# schematic.net
KiCad netlist of a schematic drawn in EAGLE
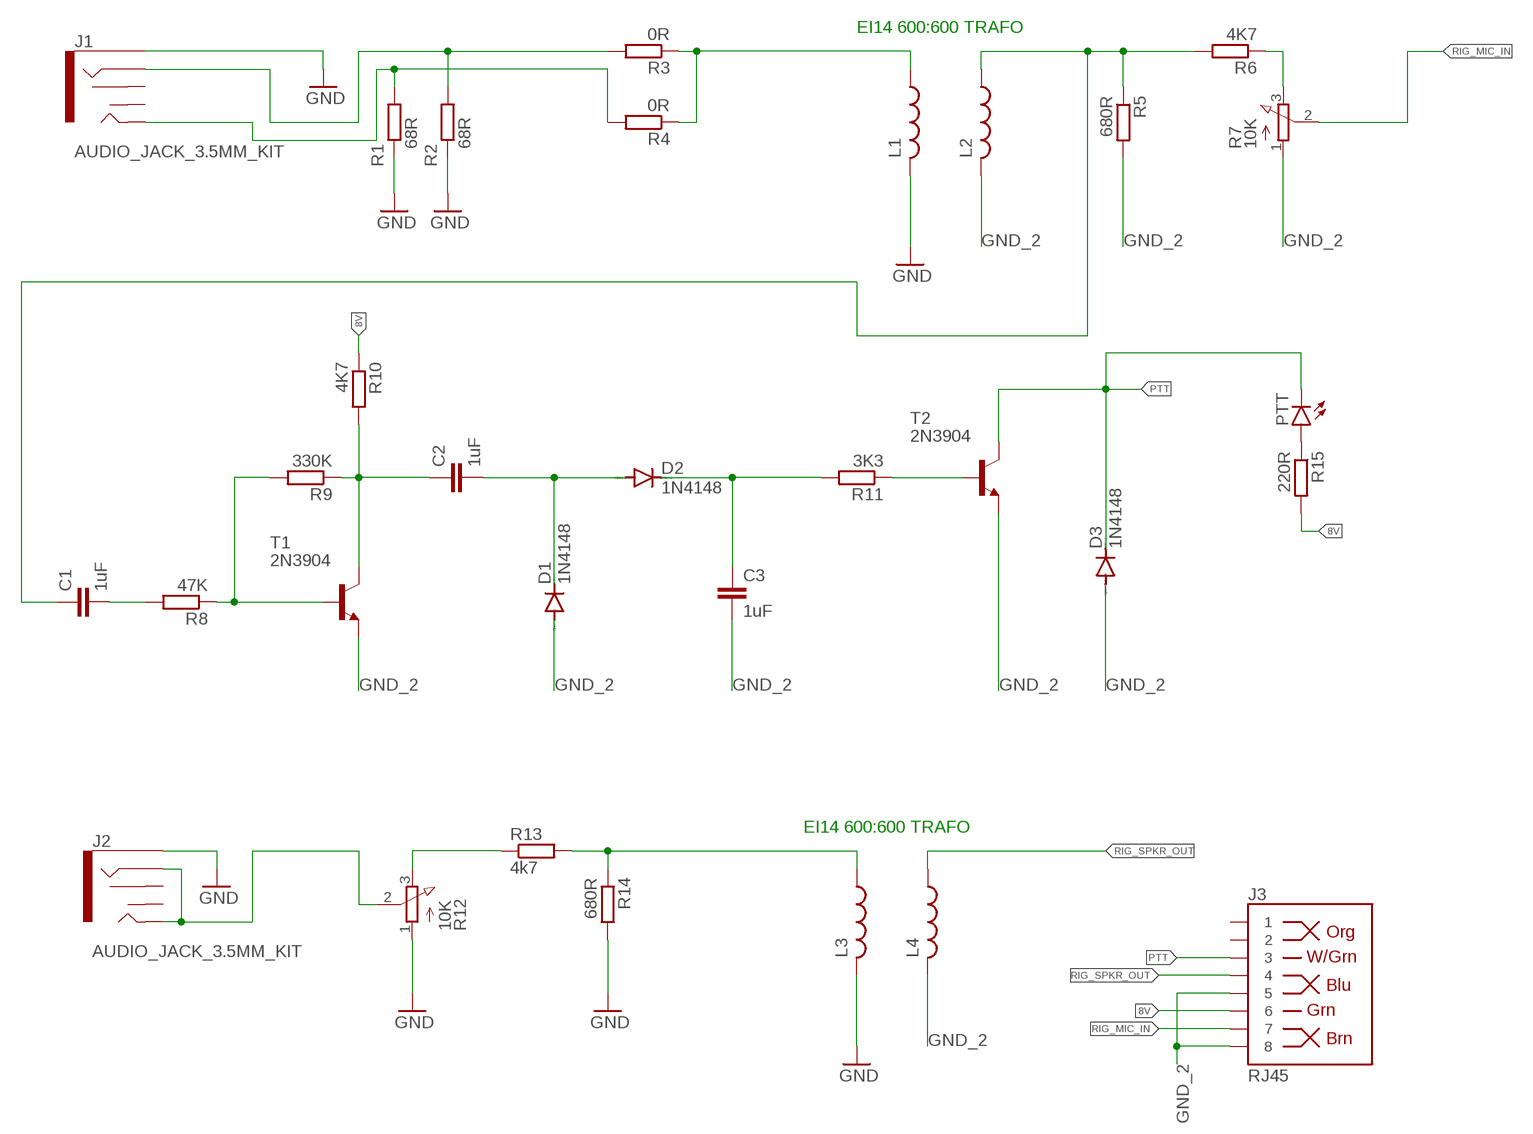
[diagram p0: schematic, sheet 1]

(export (version "E")
  (design (tool "Eeschema 10.0.6"))
  (components
    (comp (ref "C1")
      (value "1uF")
      (footprint "eagle-import:C025-030X050")
      (libsource (lib "eagle-import") (part "C-EU025-030X050"))
    )
    (comp (ref "C2")
      (value "1uF")
      (footprint "eagle-import:C025-030X050")
      (libsource (lib "eagle-import") (part "C-EU025-030X050"))
    )
    (comp (ref "C3")
      (value "1uF")
      (footprint "eagle-import:C025-030X050")
      (libsource (lib "eagle-import") (part "C-EU025-030X050"))
    )
    (comp (ref "D1")
      (value "1N4148")
      (footprint "eagle-import:DO35-7")
      (libsource (lib "eagle-import") (part "1N4148DO35-7"))
    )
    (comp (ref "D2")
      (value "1N4148")
      (footprint "eagle-import:DO35-7")
      (libsource (lib "eagle-import") (part "1N4148DO35-7"))
    )
    (comp (ref "D3")
      (value "1N4148")
      (footprint "eagle-import:DO35-7")
      (libsource (lib "eagle-import") (part "1N4148DO35-7"))
    )
    (comp (ref "J1")
      (value "AUDIO_JACK_3.5MM_KIT")
      (footprint "eagle-import:AUDIO-JACK-KIT")
      (libsource (lib "eagle-import") (part "AUDIO_JACK_3.5MM_KIT"))
    )
    (comp (ref "J2")
      (value "AUDIO_JACK_3.5MM_KIT")
      (footprint "eagle-import:AUDIO-JACK-KIT")
      (libsource (lib "eagle-import") (part "AUDIO_JACK_3.5MM_KIT"))
    )
    (comp (ref "J3")
      (value "RJ45")
      (footprint "eagle-import:RJ45-8")
      (libsource (lib "eagle-import") (part "RJ45-8"))
    )
    (comp (ref "L1")
      (value "L-US0204/5")
      (footprint "eagle-import:0204_5")
      (libsource (lib "eagle-import") (part "L-US0204/5"))
    )
    (comp (ref "L2")
      (value "L-US0204/5")
      (footprint "eagle-import:0204_5")
      (libsource (lib "eagle-import") (part "L-US0204/5"))
    )
    (comp (ref "L3")
      (value "L-US0204/5")
      (footprint "eagle-import:0204_5")
      (libsource (lib "eagle-import") (part "L-US0204/5"))
    )
    (comp (ref "L4")
      (value "L-US0204/5")
      (footprint "eagle-import:0204_5")
      (libsource (lib "eagle-import") (part "L-US0204/5"))
    )
    (comp (ref "PTT")
      (value "LED5MM")
      (footprint "eagle-import:LED5MM")
      (libsource (lib "eagle-import") (part "LED5MM"))
    )
    (comp (ref "R1")
      (value "68R")
      (footprint "eagle-import:0207_10")
      (libsource (lib "eagle-import") (part "R-EU_0207/10"))
    )
    (comp (ref "R2")
      (value "68R")
      (footprint "eagle-import:0207_10")
      (libsource (lib "eagle-import") (part "R-EU_0207/10"))
    )
    (comp (ref "R3")
      (value "0R")
      (footprint "eagle-import:R0805")
      (libsource (lib "eagle-import") (part "R-EU_R0805"))
    )
    (comp (ref "R4")
      (value "0R")
      (footprint "eagle-import:R0805")
      (libsource (lib "eagle-import") (part "R-EU_R0805"))
    )
    (comp (ref "R5")
      (value "680R")
      (footprint "eagle-import:0207_10")
      (libsource (lib "eagle-import") (part "R-EU_0207/10"))
    )
    (comp (ref "R6")
      (value "4K7")
      (footprint "eagle-import:0207_10")
      (libsource (lib "eagle-import") (part "R-EU_0207/10"))
    )
    (comp (ref "R7")
      (value "10K")
      (footprint "eagle-import:3RP_1610N")
      (libsource (lib "eagle-import") (part "3RP/1610N"))
    )
    (comp (ref "R8")
      (value "47K")
      (footprint "eagle-import:0207_10")
      (libsource (lib "eagle-import") (part "R-EU_0207/10"))
    )
    (comp (ref "R9")
      (value "330K")
      (footprint "eagle-import:0207_10")
      (libsource (lib "eagle-import") (part "R-EU_0207/10"))
    )
    (comp (ref "R10")
      (value "4K7")
      (footprint "eagle-import:0207_10")
      (libsource (lib "eagle-import") (part "R-EU_0207/10"))
    )
    (comp (ref "R11")
      (value "3K3")
      (footprint "eagle-import:0207_10")
      (libsource (lib "eagle-import") (part "R-EU_0207/10"))
    )
    (comp (ref "R12")
      (value "10K")
      (footprint "eagle-import:3RP_1610N")
      (libsource (lib "eagle-import") (part "3RP/1610N"))
    )
    (comp (ref "R13")
      (value "4k7")
      (footprint "eagle-import:0207_10")
      (libsource (lib "eagle-import") (part "R-EU_0207/10"))
    )
    (comp (ref "R14")
      (value "680R")
      (footprint "eagle-import:0207_10")
      (libsource (lib "eagle-import") (part "R-EU_0207/10"))
    )
    (comp (ref "R15")
      (value "220R")
      (footprint "eagle-import:0207_10")
      (libsource (lib "eagle-import") (part "R-EU_0207/10"))
    )
    (comp (ref "T1")
      (value "2N3904")
      (footprint "eagle-import:TO92")
      (libsource (lib "eagle-import") (part "2N3904"))
    )
    (comp (ref "T2")
      (value "2N3904")
      (footprint "eagle-import:TO92")
      (libsource (lib "eagle-import") (part "2N3904"))
    )
  )
  (nets
    (net (code "1") (name "/GND_2") (class "Default")
      (node (ref "C3") (pin "2") (pinfunction "2_2") (pintype "passive"))
      (node (ref "D1") (pin "A") (pinfunction "A_A") (pintype "passive"))
      (node (ref "D3") (pin "A") (pinfunction "A_A") (pintype "passive"))
      (node (ref "J3") (pin "5") (pinfunction "5_5") (pintype "bidirectional"))
      (node (ref "J3") (pin "8") (pinfunction "8_8") (pintype "bidirectional"))
      (node (ref "L2") (pin "2") (pinfunction "2_2") (pintype "passive"))
      (node (ref "L4") (pin "2") (pinfunction "2_2") (pintype "passive"))
      (node (ref "R5") (pin "2") (pinfunction "2_2") (pintype "passive"))
      (node (ref "R7") (pin "1") (pinfunction "A_1") (pintype "passive"))
      (node (ref "T1") (pin "3") (pinfunction "E_3") (pintype "passive"))
      (node (ref "T2") (pin "3") (pinfunction "E_3") (pintype "passive"))
    )
    (net (code "2") (name "8V") (class "Default")
      (node (ref "J3") (pin "6") (pinfunction "6_6") (pintype "bidirectional"))
      (node (ref "R10") (pin "1") (pinfunction "1_1") (pintype "passive"))
      (node (ref "R15") (pin "2") (pinfunction "2_2") (pintype "passive"))
    )
    (net (code "3") (name "GND") (class "Default")
      (node (ref "J1") (pin "SLEEVE") (pinfunction "SLEEVE_SLEEVE") (pintype "bidirectional"))
      (node (ref "J2") (pin "SLEEVE") (pinfunction "SLEEVE_SLEEVE") (pintype "bidirectional"))
      (node (ref "L1") (pin "2") (pinfunction "2_2") (pintype "passive"))
      (node (ref "L3") (pin "2") (pinfunction "2_2") (pintype "passive"))
      (node (ref "R1") (pin "1") (pinfunction "1_1") (pintype "passive"))
      (node (ref "R12") (pin "1") (pinfunction "A_1") (pintype "passive"))
      (node (ref "R14") (pin "2") (pinfunction "2_2") (pintype "passive"))
      (node (ref "R2") (pin "1") (pinfunction "1_1") (pintype "passive"))
    )
    (net (code "4") (name "Net-(C1-Pad1)") (class "Default")
      (node (ref "C1") (pin "1") (pinfunction "1_1") (pintype "passive"))
      (node (ref "L2") (pin "1") (pinfunction "1_1") (pintype "passive"))
      (node (ref "R5") (pin "1") (pinfunction "1_1") (pintype "passive"))
      (node (ref "R6") (pin "2") (pinfunction "2_2") (pintype "passive"))
    )
    (net (code "5") (name "Net-(C1-Pad2)") (class "Default")
      (node (ref "C1") (pin "2") (pinfunction "2_2") (pintype "passive"))
      (node (ref "R8") (pin "2") (pinfunction "2_2") (pintype "passive"))
    )
    (net (code "6") (name "Net-(C2-Pad2)") (class "Default")
      (node (ref "C2") (pin "2") (pinfunction "2_2") (pintype "passive"))
      (node (ref "D1") (pin "C") (pinfunction "C_C") (pintype "passive"))
      (node (ref "D2") (pin "A") (pinfunction "A_A") (pintype "passive"))
    )
    (net (code "7") (name "Net-(C3-Pad1)") (class "Default")
      (node (ref "C3") (pin "1") (pinfunction "1_1") (pintype "passive"))
      (node (ref "D2") (pin "C") (pinfunction "C_C") (pintype "passive"))
      (node (ref "R11") (pin "2") (pinfunction "2_2") (pintype "passive"))
    )
    (net (code "8") (name "Net-(J1-PadRING)") (class "Default")
      (node (ref "J1") (pin "RING") (pinfunction "RING_RING") (pintype "bidirectional"))
      (node (ref "R2") (pin "2") (pinfunction "2_2") (pintype "passive"))
      (node (ref "R3") (pin "2") (pinfunction "2_2") (pintype "passive"))
    )
    (net (code "9") (name "Net-(J1-PadTIP)") (class "Default")
      (node (ref "J1") (pin "TIP") (pinfunction "TIP_TIP") (pintype "bidirectional"))
      (node (ref "R1") (pin "2") (pinfunction "2_2") (pintype "passive"))
      (node (ref "R4") (pin "2") (pinfunction "2_2") (pintype "passive"))
    )
    (net (code "10") (name "Net-(L1-Pad1)") (class "Default")
      (node (ref "L1") (pin "1") (pinfunction "1_1") (pintype "passive"))
      (node (ref "R3") (pin "1") (pinfunction "1_1") (pintype "passive"))
      (node (ref "R4") (pin "1") (pinfunction "1_1") (pintype "passive"))
    )
    (net (code "11") (name "Net-(L3-Pad1)") (class "Default")
      (node (ref "L3") (pin "1") (pinfunction "1_1") (pintype "passive"))
      (node (ref "R13") (pin "2") (pinfunction "2_2") (pintype "passive"))
      (node (ref "R14") (pin "1") (pinfunction "1_1") (pintype "passive"))
    )
    (net (code "12") (name "Net-(PTT-PadA)") (class "Default")
      (node (ref "PTT") (pin "A") (pinfunction "A_A") (pintype "passive"))
      (node (ref "R15") (pin "1") (pinfunction "1_1") (pintype "passive"))
    )
    (net (code "13") (name "Net-(R7-E)") (class "Default")
      (node (ref "R6") (pin "1") (pinfunction "1_1") (pintype "passive"))
      (node (ref "R7") (pin "3") (pinfunction "E_3") (pintype "passive"))
    )
    (net (code "14") (name "Net-(R12-E)") (class "Default")
      (node (ref "R12") (pin "3") (pinfunction "E_3") (pintype "passive"))
      (node (ref "R13") (pin "1") (pinfunction "1_1") (pintype "passive"))
    )
    (net (code "15") (name "Net-(R12-S)") (class "Default")
      (node (ref "J2") (pin "RING") (pinfunction "RING_RING") (pintype "bidirectional"))
      (node (ref "J2") (pin "TIP") (pinfunction "TIP_TIP") (pintype "bidirectional"))
      (node (ref "R12") (pin "2") (pinfunction "S_2") (pintype "passive"))
    )
    (net (code "16") (name "Net-(T1-B)") (class "Default")
      (node (ref "R8") (pin "1") (pinfunction "1_1") (pintype "passive"))
      (node (ref "R9") (pin "2") (pinfunction "2_2") (pintype "passive"))
      (node (ref "T1") (pin "2") (pinfunction "B_2") (pintype "passive"))
    )
    (net (code "17") (name "Net-(T1-C)") (class "Default")
      (node (ref "C2") (pin "1") (pinfunction "1_1") (pintype "passive"))
      (node (ref "R10") (pin "2") (pinfunction "2_2") (pintype "passive"))
      (node (ref "R9") (pin "1") (pinfunction "1_1") (pintype "passive"))
      (node (ref "T1") (pin "1") (pinfunction "C_1") (pintype "passive"))
    )
    (net (code "18") (name "Net-(T2-B)") (class "Default")
      (node (ref "R11") (pin "1") (pinfunction "1_1") (pintype "passive"))
      (node (ref "T2") (pin "2") (pinfunction "B_2") (pintype "passive"))
    )
    (net (code "19") (name "PTT") (class "Default")
      (node (ref "D3") (pin "C") (pinfunction "C_C") (pintype "passive"))
      (node (ref "J3") (pin "3") (pinfunction "3_3") (pintype "bidirectional"))
      (node (ref "PTT") (pin "K") (pinfunction "C_K") (pintype "passive"))
      (node (ref "T2") (pin "1") (pinfunction "C_1") (pintype "passive"))
    )
    (net (code "20") (name "RIG_MIC_IN") (class "Default")
      (node (ref "J3") (pin "7") (pinfunction "7_7") (pintype "bidirectional"))
      (node (ref "R7") (pin "2") (pinfunction "S_2") (pintype "passive"))
    )
    (net (code "21") (name "RIG_SPKR_OUT") (class "Default")
      (node (ref "J3") (pin "4") (pinfunction "4_4") (pintype "bidirectional"))
      (node (ref "L4") (pin "1") (pinfunction "1_1") (pintype "passive"))
    )
    (net (code "22") (name "unconnected-(J1-PadRSH)") (class "Default")
      (node (ref "J1") (pin "RSH") (pinfunction "RSH_RSH") (pintype "bidirectional"))
    )
    (net (code "23") (name "unconnected-(J1-PadTSH)") (class "Default")
      (node (ref "J1") (pin "TSH") (pinfunction "TSH_TSH") (pintype "bidirectional"))
    )
    (net (code "24") (name "unconnected-(J2-PadRSH)") (class "Default")
      (node (ref "J2") (pin "RSH") (pinfunction "RSH_RSH") (pintype "bidirectional"))
    )
    (net (code "25") (name "unconnected-(J2-PadTSH)") (class "Default")
      (node (ref "J2") (pin "TSH") (pinfunction "TSH_TSH") (pintype "bidirectional"))
    )
    (net (code "26") (name "unconnected-(J3-Pad1)") (class "Default")
      (node (ref "J3") (pin "1") (pinfunction "1_1") (pintype "bidirectional"))
    )
    (net (code "27") (name "unconnected-(J3-Pad2)") (class "Default")
      (node (ref "J3") (pin "2") (pinfunction "2_2") (pintype "bidirectional"))
    )
  )
)
